# 52204_Breakout.net
KiCad netlist of a schematic drawn in Altium Designer
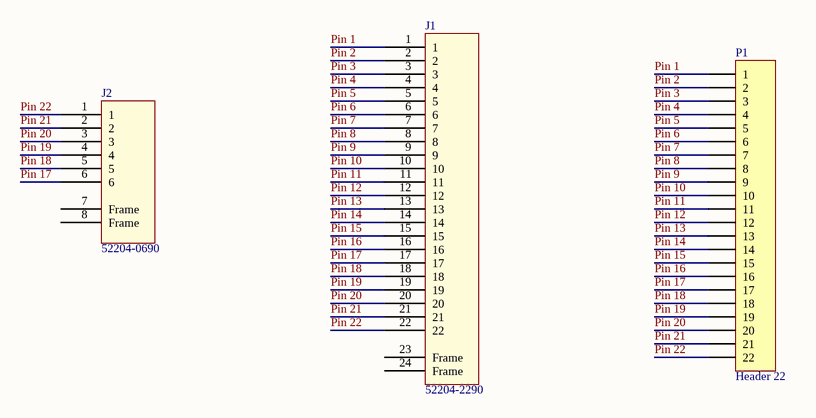
[diagram p0: 52204 Breakout.SchDoc]

(export (version "E")
  (design (tool "Eeschema 10.0.6"))
  (components
    (comp (ref "J1")
      (value "52204-2290")
      (footprint "52204-2290")
      (libsource (lib "KBuchka-IntLib") (part "52204-2290"))
    )
    (comp (ref "J2")
      (value "52204-0690")
      (footprint "52204-0690")
      (libsource (lib "KBuchka-IntLib") (part "52204-0690"))
    )
    (comp (ref "P1")
      (value "Header 22")
      (footprint "HDR1X22")
      (description "Header, 22-Pin")
      (fields (field (name "PUBLISHER") "Altium Limited"))
      (libsource (lib "Miscellaneous Connectors") (part "Header 22"))
    )
  )
  (nets
    (net (code "1") (name "/Pin 1") (class "Default")
      (node (ref "J1") (pin "1") (pinfunction "1_1") (pintype "passive"))
      (node (ref "P1") (pin "1") (pinfunction "1_1") (pintype "passive"))
    )
    (net (code "2") (name "/Pin 2") (class "Default")
      (node (ref "J1") (pin "2") (pinfunction "2_2") (pintype "passive"))
      (node (ref "P1") (pin "2") (pinfunction "2_2") (pintype "passive"))
    )
    (net (code "3") (name "/Pin 3") (class "Default")
      (node (ref "J1") (pin "3") (pinfunction "3_3") (pintype "passive"))
      (node (ref "P1") (pin "3") (pinfunction "3_3") (pintype "passive"))
    )
    (net (code "4") (name "/Pin 4") (class "Default")
      (node (ref "J1") (pin "4") (pinfunction "4_4") (pintype "passive"))
      (node (ref "P1") (pin "4") (pinfunction "4_4") (pintype "passive"))
    )
    (net (code "5") (name "/Pin 5") (class "Default")
      (node (ref "J1") (pin "5") (pinfunction "5_5") (pintype "passive"))
      (node (ref "P1") (pin "5") (pinfunction "5_5") (pintype "passive"))
    )
    (net (code "6") (name "/Pin 6") (class "Default")
      (node (ref "J1") (pin "6") (pinfunction "6_6") (pintype "passive"))
      (node (ref "P1") (pin "6") (pinfunction "6_6") (pintype "passive"))
    )
    (net (code "7") (name "/Pin 7") (class "Default")
      (node (ref "J1") (pin "7") (pinfunction "7_7") (pintype "passive"))
      (node (ref "P1") (pin "7") (pinfunction "7_7") (pintype "passive"))
    )
    (net (code "8") (name "/Pin 8") (class "Default")
      (node (ref "J1") (pin "8") (pinfunction "8_8") (pintype "passive"))
      (node (ref "P1") (pin "8") (pinfunction "8_8") (pintype "passive"))
    )
    (net (code "9") (name "/Pin 9") (class "Default")
      (node (ref "J1") (pin "9") (pinfunction "9_9") (pintype "passive"))
      (node (ref "P1") (pin "9") (pinfunction "9_9") (pintype "passive"))
    )
    (net (code "10") (name "/Pin 10") (class "Default")
      (node (ref "J1") (pin "10") (pinfunction "10_10") (pintype "passive"))
      (node (ref "P1") (pin "10") (pinfunction "10_10") (pintype "passive"))
    )
    (net (code "11") (name "/Pin 11") (class "Default")
      (node (ref "J1") (pin "11") (pinfunction "11_11") (pintype "passive"))
      (node (ref "P1") (pin "11") (pinfunction "11_11") (pintype "passive"))
    )
    (net (code "12") (name "/Pin 12") (class "Default")
      (node (ref "J1") (pin "12") (pinfunction "12_12") (pintype "passive"))
      (node (ref "P1") (pin "12") (pinfunction "12_12") (pintype "passive"))
    )
    (net (code "13") (name "/Pin 13") (class "Default")
      (node (ref "J1") (pin "13") (pinfunction "13_13") (pintype "passive"))
      (node (ref "P1") (pin "13") (pinfunction "13_13") (pintype "passive"))
    )
    (net (code "14") (name "/Pin 14") (class "Default")
      (node (ref "J1") (pin "14") (pinfunction "14_14") (pintype "passive"))
      (node (ref "P1") (pin "14") (pinfunction "14_14") (pintype "passive"))
    )
    (net (code "15") (name "/Pin 15") (class "Default")
      (node (ref "J1") (pin "15") (pinfunction "15_15") (pintype "passive"))
      (node (ref "P1") (pin "15") (pinfunction "15_15") (pintype "passive"))
    )
    (net (code "16") (name "/Pin 16") (class "Default")
      (node (ref "J1") (pin "16") (pinfunction "16_16") (pintype "passive"))
      (node (ref "P1") (pin "16") (pinfunction "16_16") (pintype "passive"))
    )
    (net (code "17") (name "/Pin 17") (class "Default")
      (node (ref "J1") (pin "17") (pinfunction "17_17") (pintype "passive"))
      (node (ref "J2") (pin "6") (pinfunction "6_6") (pintype "passive"))
      (node (ref "P1") (pin "17") (pinfunction "17_17") (pintype "passive"))
    )
    (net (code "18") (name "/Pin 18") (class "Default")
      (node (ref "J1") (pin "18") (pinfunction "18_18") (pintype "passive"))
      (node (ref "J2") (pin "5") (pinfunction "5_5") (pintype "passive"))
      (node (ref "P1") (pin "18") (pinfunction "18_18") (pintype "passive"))
    )
    (net (code "19") (name "/Pin 19") (class "Default")
      (node (ref "J1") (pin "19") (pinfunction "19_19") (pintype "passive"))
      (node (ref "J2") (pin "4") (pinfunction "4_4") (pintype "passive"))
      (node (ref "P1") (pin "19") (pinfunction "19_19") (pintype "passive"))
    )
    (net (code "20") (name "/Pin 20") (class "Default")
      (node (ref "J1") (pin "20") (pinfunction "20_20") (pintype "passive"))
      (node (ref "J2") (pin "3") (pinfunction "3_3") (pintype "passive"))
      (node (ref "P1") (pin "20") (pinfunction "20_20") (pintype "passive"))
    )
    (net (code "21") (name "/Pin 21") (class "Default")
      (node (ref "J1") (pin "21") (pinfunction "21_21") (pintype "passive"))
      (node (ref "J2") (pin "2") (pinfunction "2_2") (pintype "passive"))
      (node (ref "P1") (pin "21") (pinfunction "21_21") (pintype "passive"))
    )
    (net (code "22") (name "/Pin 22") (class "Default")
      (node (ref "J1") (pin "22") (pinfunction "22_22") (pintype "passive"))
      (node (ref "J2") (pin "1") (pinfunction "1_1") (pintype "passive"))
      (node (ref "P1") (pin "22") (pinfunction "22_22") (pintype "passive"))
    )
    (net (code "23") (name "unconnected-(J1-Frame-Pad23)") (class "Default")
      (node (ref "J1") (pin "23") (pinfunction "Frame_23") (pintype "passive"))
    )
    (net (code "24") (name "unconnected-(J1-Frame-Pad24)") (class "Default")
      (node (ref "J1") (pin "24") (pinfunction "Frame_24") (pintype "passive"))
    )
    (net (code "25") (name "unconnected-(J2-Frame-Pad7)") (class "Default")
      (node (ref "J2") (pin "7") (pinfunction "Frame_7") (pintype "passive"))
    )
    (net (code "26") (name "unconnected-(J2-Frame-Pad8)") (class "Default")
      (node (ref "J2") (pin "8") (pinfunction "Frame_8") (pintype "passive"))
    )
  )
)
